# MUTE-basic.net
KiCad netlist of a schematic drawn in EAGLE
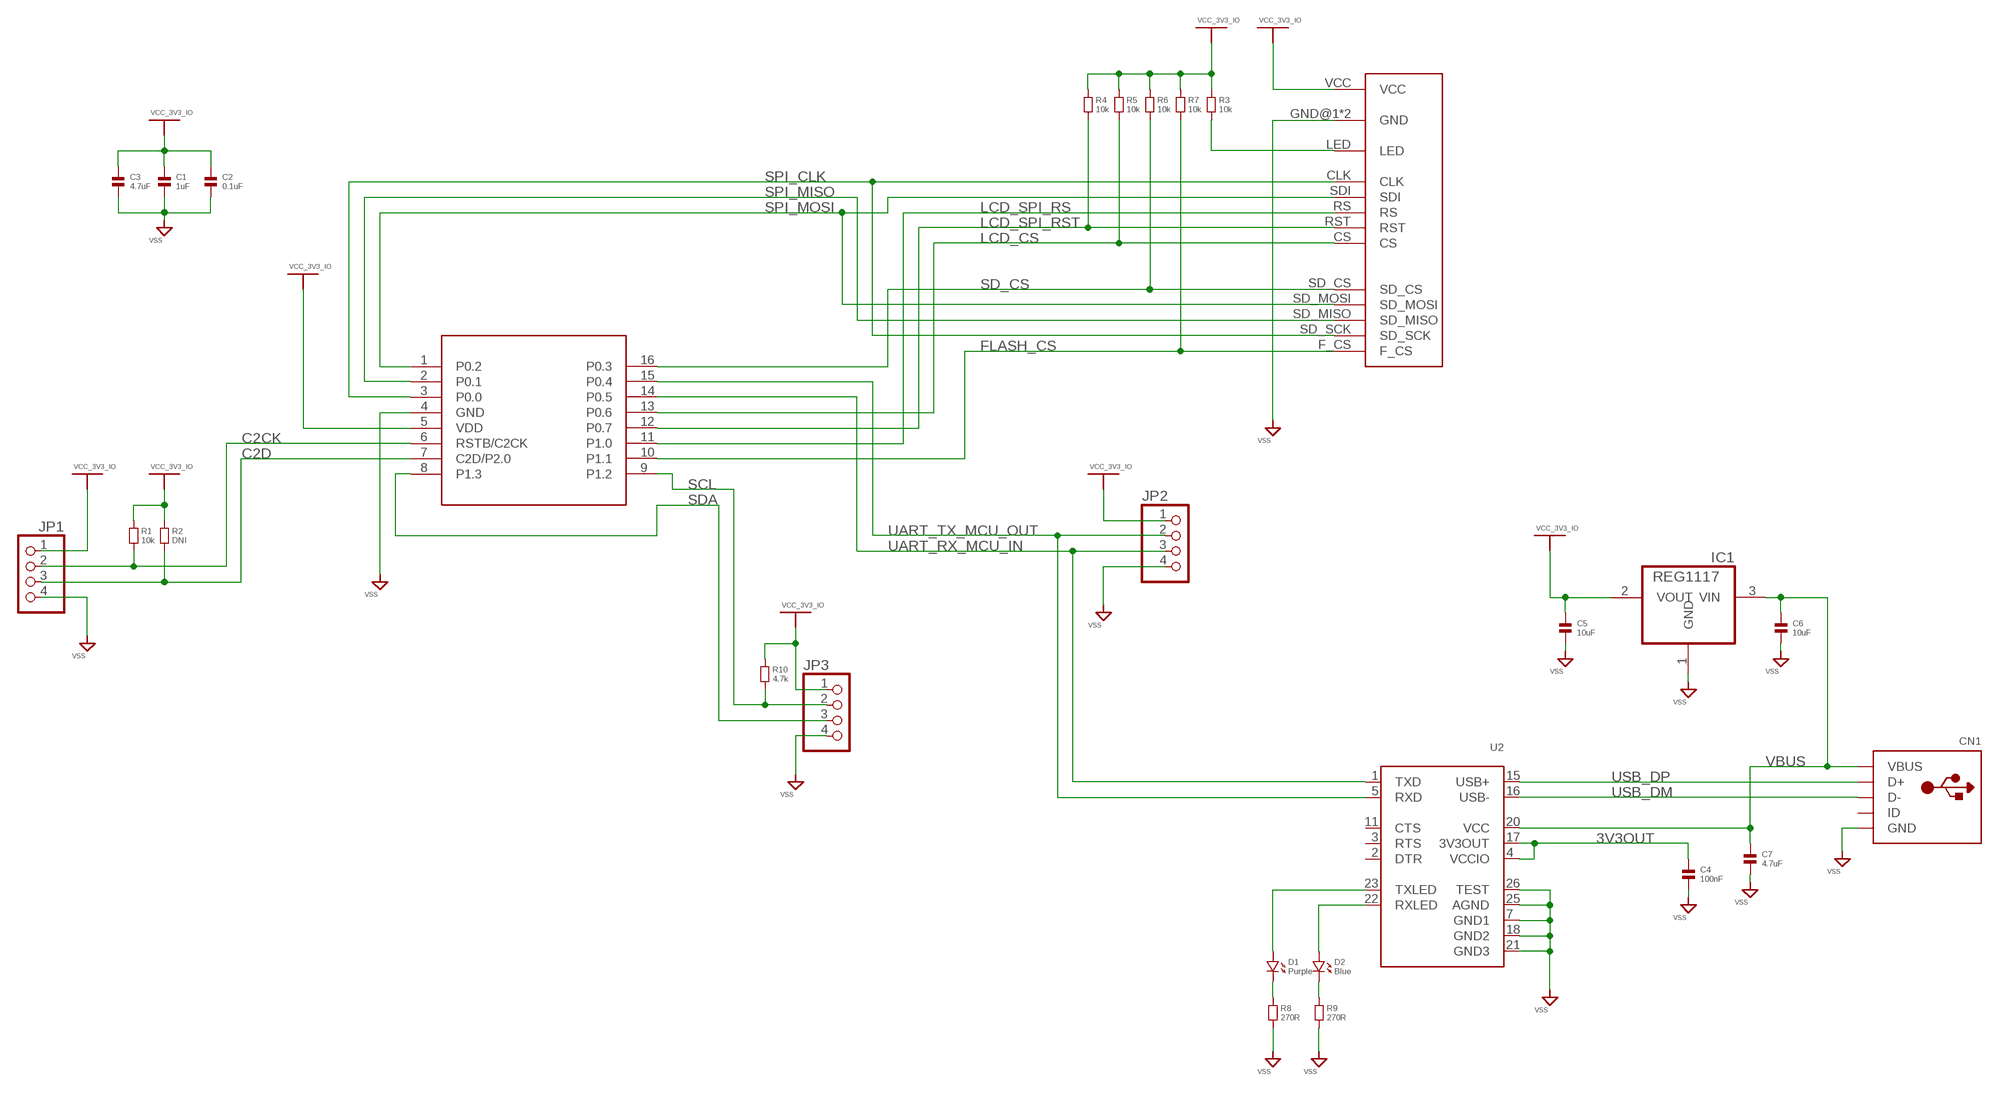
[diagram p0: schematic, sheet 1]

(export (version "E")
  (design (tool "Eeschema 10.0.6"))
  (components
    (comp (ref "C1")
      (value "1uF")
      (footprint "eagle-import:0603")
      (libsource (lib "eagle-import") (part "CAPACITOR.0603"))
    )
    (comp (ref "C2")
      (value "0.1uF")
      (footprint "eagle-import:0603")
      (libsource (lib "eagle-import") (part "CAPACITOR.0603"))
    )
    (comp (ref "C3")
      (value "4.7uF")
      (footprint "eagle-import:0603")
      (libsource (lib "eagle-import") (part "CAPACITOR.0603"))
    )
    (comp (ref "C4")
      (value "100nF")
      (footprint "eagle-import:0603")
      (libsource (lib "eagle-import") (part "CAPACITOR.0603"))
    )
    (comp (ref "C5")
      (value "10uF")
      (footprint "eagle-import:0603")
      (libsource (lib "eagle-import") (part "CAPACITOR.0603"))
    )
    (comp (ref "C6")
      (value "10uF")
      (footprint "eagle-import:0603")
      (libsource (lib "eagle-import") (part "CAPACITOR.0603"))
    )
    (comp (ref "C7")
      (value "4.7uF")
      (footprint "eagle-import:0603")
      (libsource (lib "eagle-import") (part "CAPACITOR.0603"))
    )
    (comp (ref "CN1")
      (value "USBMINIB")
      (footprint "eagle-import:USB-MINIB")
      (libsource (lib "eagle-import") (part "USBMINIB"))
    )
    (comp (ref "D1")
      (value "Purple")
      (footprint "eagle-import:0603.LED")
      (libsource (lib "eagle-import") (part "LED.0603"))
    )
    (comp (ref "D2")
      (value "Blue")
      (footprint "eagle-import:0603.LED")
      (libsource (lib "eagle-import") (part "LED.0603"))
    )
    (comp (ref "IC1")
      (value "REG1117")
      (footprint "eagle-import:SOT223")
      (libsource (lib "eagle-import") (part "REG1117"))
    )
    (comp (ref "JP1")
      (value "PINHD-1X4")
      (footprint "eagle-import:1X04")
      (libsource (lib "eagle-import") (part "PINHD-1X4"))
    )
    (comp (ref "JP2")
      (value "PINHD-1X4")
      (footprint "eagle-import:1X04")
      (libsource (lib "eagle-import") (part "PINHD-1X4"))
    )
    (comp (ref "JP3")
      (value "PINHD-1X4")
      (footprint "eagle-import:1X04")
      (libsource (lib "eagle-import") (part "PINHD-1X4"))
    )
    (comp (ref "R1")
      (value "10k")
      (footprint "eagle-import:0603")
      (libsource (lib "eagle-import") (part "RESISTOR.0603"))
    )
    (comp (ref "R2")
      (value "DNI")
      (footprint "eagle-import:0603")
      (libsource (lib "eagle-import") (part "RESISTOR.0603"))
    )
    (comp (ref "R3")
      (value "10k")
      (footprint "eagle-import:0603")
      (libsource (lib "eagle-import") (part "RESISTOR.0603"))
    )
    (comp (ref "R4")
      (value "10k")
      (footprint "eagle-import:0603")
      (libsource (lib "eagle-import") (part "RESISTOR.0603"))
    )
    (comp (ref "R5")
      (value "10k")
      (footprint "eagle-import:0603")
      (libsource (lib "eagle-import") (part "RESISTOR.0603"))
    )
    (comp (ref "R6")
      (value "10k")
      (footprint "eagle-import:0603")
      (libsource (lib "eagle-import") (part "RESISTOR.0603"))
    )
    (comp (ref "R7")
      (value "10k")
      (footprint "eagle-import:0603")
      (libsource (lib "eagle-import") (part "RESISTOR.0603"))
    )
    (comp (ref "R8")
      (value "270R")
      (footprint "eagle-import:0603")
      (libsource (lib "eagle-import") (part "RESISTOR.0603"))
    )
    (comp (ref "R9")
      (value "270R")
      (footprint "eagle-import:0603")
      (libsource (lib "eagle-import") (part "RESISTOR.0603"))
    )
    (comp (ref "R10")
      (value "4.7k")
      (footprint "eagle-import:0603")
      (libsource (lib "eagle-import") (part "RESISTOR.0603"))
    )
    (comp (ref "U$1")
      (value "WINGONEER_ILI9225")
      (footprint "eagle-import:WINGONEER_ILI9225")
      (libsource (lib "eagle-import") (part "WINGONEER_ILI9225"))
    )
    (comp (ref "U1")
      (value "SILICON_LABS-MICROCONTROLLER-EFM8BB10F8G-SOIC16")
      (footprint "eagle-import:SILICON_LABS-MICROCONTROLLER-EFM8BB10F8G-A-SOIC16")
      (libsource (lib "eagle-import") (part "SILICON_LABS-MICROCONTROLLER-EFM8BB10F8G-SOIC16"))
    )
    (comp (ref "U2")
      (value "FT232RLSSOP28")
      (footprint "eagle-import:SSOP28DB")
      (libsource (lib "eagle-import") (part "FT232RLSSOP28"))
    )
  )
  (nets
    (net (code "1") (name "/3V3OUT") (class "Default")
      (node (ref "C4") (pin "1") (pinfunction "1_1") (pintype "bidirectional"))
      (node (ref "U2") (pin "17") (pinfunction "3V3OUT_17") (pintype "power_in"))
      (node (ref "U2") (pin "4") (pinfunction "VCCIO_4") (pintype "power_in"))
    )
    (net (code "2") (name "/C2CK") (class "Default")
      (node (ref "JP1") (pin "2") (pinfunction "2_2") (pintype "passive"))
      (node (ref "R1") (pin "2") (pinfunction "2_2") (pintype "bidirectional"))
      (node (ref "U1") (pin "6") (pinfunction "RSTB/C2CK_6") (pintype "bidirectional"))
    )
    (net (code "3") (name "/C2D") (class "Default")
      (node (ref "JP1") (pin "3") (pinfunction "3_3") (pintype "passive"))
      (node (ref "R2") (pin "2") (pinfunction "2_2") (pintype "bidirectional"))
      (node (ref "U1") (pin "7") (pinfunction "C2D/P2.0_7") (pintype "bidirectional"))
    )
    (net (code "4") (name "/FLASH_CS") (class "Default")
      (node (ref "R7") (pin "2") (pinfunction "2_2") (pintype "bidirectional"))
      (node (ref "U$1") (pin "F_CS") (pinfunction "F_CS_F_CS") (pintype "bidirectional"))
      (node (ref "U1") (pin "10") (pinfunction "P1.1_10") (pintype "bidirectional"))
    )
    (net (code "5") (name "/LCD_CS") (class "Default")
      (node (ref "R5") (pin "2") (pinfunction "2_2") (pintype "bidirectional"))
      (node (ref "U$1") (pin "CS") (pinfunction "CS_CS") (pintype "bidirectional"))
      (node (ref "U1") (pin "13") (pinfunction "P0.6_13") (pintype "bidirectional"))
    )
    (net (code "6") (name "/LCD_SPI_RS") (class "Default")
      (node (ref "U$1") (pin "RS") (pinfunction "RS_RS") (pintype "bidirectional"))
      (node (ref "U1") (pin "11") (pinfunction "P1.0_11") (pintype "bidirectional"))
    )
    (net (code "7") (name "/LCD_SPI_RST") (class "Default")
      (node (ref "R4") (pin "2") (pinfunction "2_2") (pintype "bidirectional"))
      (node (ref "U$1") (pin "RST") (pinfunction "RST_RST") (pintype "bidirectional"))
      (node (ref "U1") (pin "12") (pinfunction "P0.7_12") (pintype "bidirectional"))
    )
    (net (code "8") (name "/SCL") (class "Default")
      (node (ref "JP3") (pin "2") (pinfunction "2_2") (pintype "passive"))
      (node (ref "R10") (pin "2") (pinfunction "2_2") (pintype "bidirectional"))
      (node (ref "U1") (pin "9") (pinfunction "P1.2_9") (pintype "bidirectional"))
    )
    (net (code "9") (name "/SDA") (class "Default")
      (node (ref "JP3") (pin "3") (pinfunction "3_3") (pintype "passive"))
      (node (ref "U1") (pin "8") (pinfunction "P1.3_8") (pintype "bidirectional"))
    )
    (net (code "10") (name "/SD_CS") (class "Default")
      (node (ref "R6") (pin "2") (pinfunction "2_2") (pintype "bidirectional"))
      (node (ref "U$1") (pin "SD_CS") (pinfunction "SD_CS_SD_CS") (pintype "bidirectional"))
      (node (ref "U1") (pin "16") (pinfunction "P0.3_16") (pintype "bidirectional"))
    )
    (net (code "11") (name "/SPI_CLK") (class "Default")
      (node (ref "U$1") (pin "CLK") (pinfunction "CLK_CLK") (pintype "bidirectional"))
      (node (ref "U$1") (pin "SD_SCK") (pinfunction "SD_SCK_SD_SCK") (pintype "bidirectional"))
      (node (ref "U1") (pin "3") (pinfunction "P0.0_3") (pintype "bidirectional"))
    )
    (net (code "12") (name "/SPI_MISO") (class "Default")
      (node (ref "U$1") (pin "SD_MISO") (pinfunction "SD_MISO_SD_MISO") (pintype "bidirectional"))
      (node (ref "U1") (pin "2") (pinfunction "P0.1_2") (pintype "bidirectional"))
    )
    (net (code "13") (name "/SPI_MOSI") (class "Default")
      (node (ref "U$1") (pin "SDI") (pinfunction "SDI_SDI") (pintype "bidirectional"))
      (node (ref "U$1") (pin "SD_MOSI") (pinfunction "SD_MOSI_SD_MOSI") (pintype "bidirectional"))
      (node (ref "U1") (pin "1") (pinfunction "P0.2_1") (pintype "bidirectional"))
    )
    (net (code "14") (name "/UART_RX_MCU_IN") (class "Default")
      (node (ref "JP2") (pin "3") (pinfunction "3_3") (pintype "passive"))
      (node (ref "U1") (pin "14") (pinfunction "P0.5_14") (pintype "bidirectional"))
      (node (ref "U2") (pin "1") (pinfunction "TXD_1") (pintype "output"))
    )
    (net (code "15") (name "/UART_TX_MCU_OUT") (class "Default")
      (node (ref "JP2") (pin "2") (pinfunction "2_2") (pintype "passive"))
      (node (ref "U1") (pin "15") (pinfunction "P0.4_15") (pintype "bidirectional"))
      (node (ref "U2") (pin "5") (pinfunction "RXD_5") (pintype "input"))
    )
    (net (code "16") (name "/USB_DM") (class "Default")
      (node (ref "CN1") (pin "D-") (pinfunction "D-_D-") (pintype "bidirectional"))
      (node (ref "U2") (pin "16") (pinfunction "USB-_16") (pintype "bidirectional"))
    )
    (net (code "17") (name "/USB_DP") (class "Default")
      (node (ref "CN1") (pin "D+") (pinfunction "D+_D+") (pintype "bidirectional"))
      (node (ref "U2") (pin "15") (pinfunction "USB+_15") (pintype "bidirectional"))
    )
    (net (code "18") (name "/VBUS") (class "Default")
      (node (ref "C6") (pin "1") (pinfunction "1_1") (pintype "bidirectional"))
      (node (ref "C7") (pin "1") (pinfunction "1_1") (pintype "bidirectional"))
      (node (ref "CN1") (pin "VBUS") (pinfunction "VBUS_VBUS") (pintype "power_in"))
      (node (ref "IC1") (pin "3") (pinfunction "VIN_3") (pintype "input"))
      (node (ref "U2") (pin "20") (pinfunction "VCC_20") (pintype "power_in"))
    )
    (net (code "19") (name "Net-(D1-1)") (class "Default")
      (node (ref "D1") (pin "P$1") (pinfunction "1_P$1") (pintype "bidirectional"))
      (node (ref "U2") (pin "23") (pinfunction "TXLED_23") (pintype "bidirectional"))
    )
    (net (code "20") (name "Net-(D1-2)") (class "Default")
      (node (ref "D1") (pin "P$2") (pinfunction "2_P$2") (pintype "bidirectional"))
      (node (ref "R8") (pin "1") (pinfunction "1_1") (pintype "bidirectional"))
    )
    (net (code "21") (name "Net-(D2-1)") (class "Default")
      (node (ref "D2") (pin "P$1") (pinfunction "1_P$1") (pintype "bidirectional"))
      (node (ref "U2") (pin "22") (pinfunction "RXLED_22") (pintype "bidirectional"))
    )
    (net (code "22") (name "Net-(D2-2)") (class "Default")
      (node (ref "D2") (pin "P$2") (pinfunction "2_P$2") (pintype "bidirectional"))
      (node (ref "R9") (pin "1") (pinfunction "1_1") (pintype "bidirectional"))
    )
    (net (code "23") (name "Net-(R3-Pad2)") (class "Default")
      (node (ref "R3") (pin "2") (pinfunction "2_2") (pintype "bidirectional"))
      (node (ref "U$1") (pin "LED") (pinfunction "LED_LED") (pintype "bidirectional"))
    )
    (net (code "24") (name "VCC_3V3_IO") (class "Default")
      (node (ref "C1") (pin "1") (pinfunction "1_1") (pintype "bidirectional"))
      (node (ref "C2") (pin "1") (pinfunction "1_1") (pintype "bidirectional"))
      (node (ref "C3") (pin "1") (pinfunction "1_1") (pintype "bidirectional"))
      (node (ref "C5") (pin "1") (pinfunction "1_1") (pintype "bidirectional"))
      (node (ref "IC1") (pin "2") (pinfunction "VOUT_2") (pintype "output"))
      (node (ref "JP1") (pin "1") (pinfunction "1_1") (pintype "passive"))
      (node (ref "JP2") (pin "1") (pinfunction "1_1") (pintype "passive"))
      (node (ref "JP3") (pin "1") (pinfunction "1_1") (pintype "passive"))
      (node (ref "R1") (pin "1") (pinfunction "1_1") (pintype "bidirectional"))
      (node (ref "R10") (pin "1") (pinfunction "1_1") (pintype "bidirectional"))
      (node (ref "R2") (pin "1") (pinfunction "1_1") (pintype "bidirectional"))
      (node (ref "R3") (pin "1") (pinfunction "1_1") (pintype "bidirectional"))
      (node (ref "R4") (pin "1") (pinfunction "1_1") (pintype "bidirectional"))
      (node (ref "R5") (pin "1") (pinfunction "1_1") (pintype "bidirectional"))
      (node (ref "R6") (pin "1") (pinfunction "1_1") (pintype "bidirectional"))
      (node (ref "R7") (pin "1") (pinfunction "1_1") (pintype "bidirectional"))
      (node (ref "U$1") (pin "VCC") (pinfunction "VCC_VCC") (pintype "bidirectional"))
      (node (ref "U1") (pin "5") (pinfunction "VDD_5") (pintype "bidirectional"))
    )
    (net (code "25") (name "VSS") (class "Default")
      (node (ref "C1") (pin "2") (pinfunction "2_2") (pintype "bidirectional"))
      (node (ref "C2") (pin "2") (pinfunction "2_2") (pintype "bidirectional"))
      (node (ref "C3") (pin "2") (pinfunction "2_2") (pintype "bidirectional"))
      (node (ref "C4") (pin "2") (pinfunction "2_2") (pintype "bidirectional"))
      (node (ref "C5") (pin "2") (pinfunction "2_2") (pintype "bidirectional"))
      (node (ref "C6") (pin "2") (pinfunction "2_2") (pintype "bidirectional"))
      (node (ref "C7") (pin "2") (pinfunction "2_2") (pintype "bidirectional"))
      (node (ref "CN1") (pin "GND") (pinfunction "GND_GND") (pintype "power_in"))
      (node (ref "IC1") (pin "1") (pinfunction "GND_1") (pintype "power_in"))
      (node (ref "JP1") (pin "4") (pinfunction "4_4") (pintype "passive"))
      (node (ref "JP2") (pin "4") (pinfunction "4_4") (pintype "passive"))
      (node (ref "JP3") (pin "4") (pinfunction "4_4") (pintype "passive"))
      (node (ref "R8") (pin "2") (pinfunction "2_2") (pintype "bidirectional"))
      (node (ref "R9") (pin "2") (pinfunction "2_2") (pintype "bidirectional"))
      (node (ref "U$1") (pin "GND@1") (pinfunction "GND_GND@1") (pintype "bidirectional"))
      (node (ref "U$1") (pin "GND@2") (pinfunction "GND_GND@2") (pintype "bidirectional"))
      (node (ref "U1") (pin "4") (pinfunction "GND_4") (pintype "bidirectional"))
      (node (ref "U2") (pin "18") (pinfunction "GND2_18") (pintype "power_in"))
      (node (ref "U2") (pin "21") (pinfunction "GND3_21") (pintype "power_in"))
      (node (ref "U2") (pin "25") (pinfunction "AGND_25") (pintype "power_in"))
      (node (ref "U2") (pin "26") (pinfunction "TEST_26") (pintype "input"))
      (node (ref "U2") (pin "7") (pinfunction "GND1_7") (pintype "power_in"))
    )
    (net (code "26") (name "unconnected-(CN1-PadID)") (class "Default")
      (node (ref "CN1") (pin "ID") (pinfunction "ID_ID") (pintype "bidirectional"))
    )
    (net (code "27") (name "unconnected-(U2-CTS-Pad11)") (class "Default")
      (node (ref "U2") (pin "11") (pinfunction "CTS_11") (pintype "bidirectional"))
    )
    (net (code "28") (name "unconnected-(U2-DTR-Pad2)") (class "Default")
      (node (ref "U2") (pin "2") (pinfunction "DTR_2") (pintype "bidirectional"))
    )
    (net (code "29") (name "unconnected-(U2-RTS-Pad3)") (class "Default")
      (node (ref "U2") (pin "3") (pinfunction "RTS_3") (pintype "bidirectional"))
    )
  )
)
